# Part1_3210105209.net
KiCad netlist of a schematic drawn in Altium Designer
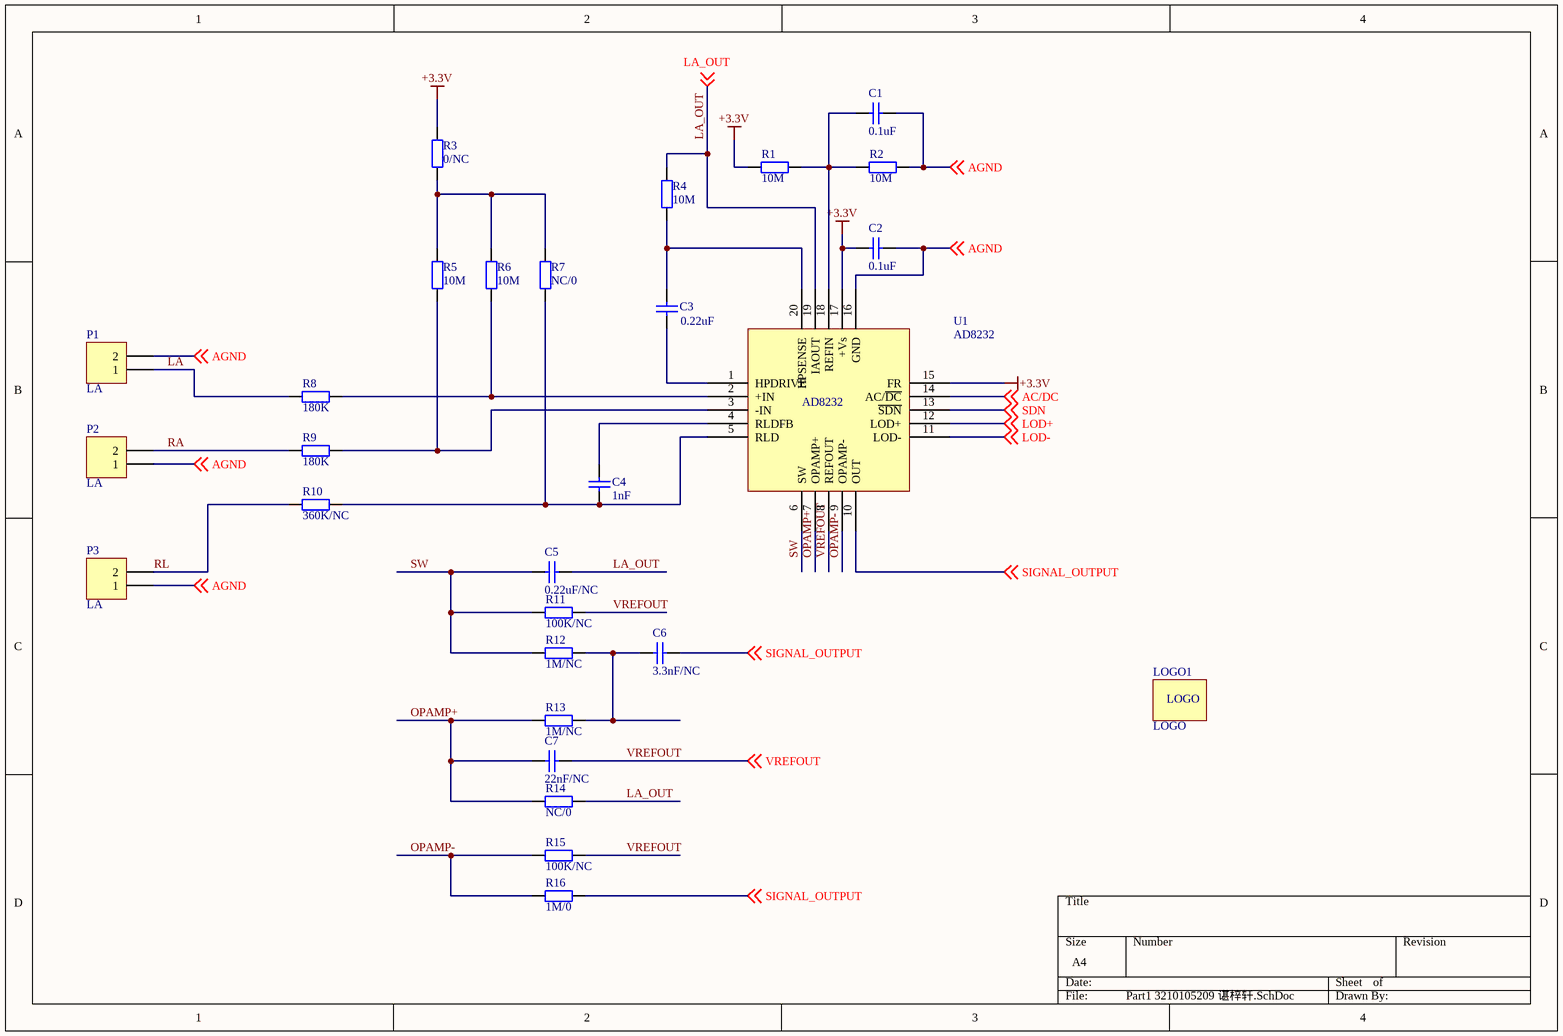
[diagram p0: Part1 3210105209 谌梓轩.SchDoc]

(export (version "E")
  (design (tool "Eeschema 10.0.6"))
  (components
    (comp (ref "C1")
      (value "0.1uF")
      (footprint "0603C")
      (description "Capacitor")
      (fields (field (name "PUBLISHER") "Altium Limited"))
      (libsource (lib "ECG2.0_1") (part "Cap"))
    )
    (comp (ref "C2")
      (value "0.1uF")
      (footprint "0603C")
      (description "Capacitor")
      (fields (field (name "PUBLISHER") "Altium Limited"))
      (libsource (lib "ECG2.0_1") (part "Cap"))
    )
    (comp (ref "C3")
      (value "0.22uF")
      (footprint "0603C")
      (description "Capacitor")
      (fields (field (name "PUBLISHER") "Altium Limited"))
      (libsource (lib "ECG2.0_1") (part "Cap"))
    )
    (comp (ref "C4")
      (value "1nF")
      (footprint "0603C")
      (description "Capacitor")
      (fields (field (name "PUBLISHER") "Altium Limited"))
      (libsource (lib "ECG2.0_1") (part "Cap"))
    )
    (comp (ref "C5")
      (value "0.22uF/NC")
      (footprint "0603C")
      (description "Capacitor")
      (fields (field (name "PUBLISHER") "Altium Limited"))
      (libsource (lib "ECG2.0_1") (part "Cap"))
    )
    (comp (ref "C6")
      (value "3.3nF/NC")
      (footprint "0603C")
      (description "Capacitor")
      (fields (field (name "PUBLISHER") "Altium Limited"))
      (libsource (lib "ECG2.0_1") (part "Cap"))
    )
    (comp (ref "C7")
      (value "22nF/NC")
      (footprint "0603C")
      (description "Capacitor")
      (fields (field (name "PUBLISHER") "Altium Limited"))
      (libsource (lib "ECG2.0_1") (part "Cap"))
    )
    (comp (ref "LOGO1") (value "LOGO") (footprint "LOGO") (libsource (lib "ECG2.0_1") (part "LOGO")))
    (comp (ref "P1")
      (value "LA")
      (footprint "SIP2")
      (description "Header, 2-Pin")
      (fields (field (name "PUBLISHER") "Altium Limited"))
      (libsource (lib "ECG2.0_1") (part "Header 2"))
    )
    (comp (ref "P2")
      (value "LA")
      (footprint "SIP2")
      (description "Header, 2-Pin")
      (fields (field (name "PUBLISHER") "Altium Limited"))
      (libsource (lib "ECG2.0_1") (part "Header 2"))
    )
    (comp (ref "P3")
      (value "LA")
      (footprint "SIP2")
      (description "Header, 2-Pin")
      (fields (field (name "PUBLISHER") "Altium Limited"))
      (libsource (lib "ECG2.0_1") (part "Header 2"))
    )
    (comp (ref "R1")
      (value "10M")
      (footprint "0603R")
      (description "Resistor")
      (fields (field (name "PUBLISHER") "Altium Limited"))
      (libsource (lib "") (part "Res2_1"))
    )
    (comp (ref "R2")
      (value "10M")
      (footprint "0603R")
      (description "Resistor")
      (fields (field (name "PUBLISHER") "Altium Limited"))
      (libsource (lib "") (part "Res2_1"))
    )
    (comp (ref "R3")
      (value "0/NC")
      (footprint "0603R")
      (description "Resistor")
      (fields (field (name "PUBLISHER") "Altium Limited"))
      (libsource (lib "ECG2.0_1") (part "Res2"))
    )
    (comp (ref "R4")
      (value "10M")
      (footprint "0603R")
      (description "Resistor")
      (fields (field (name "PUBLISHER") "Altium Limited"))
      (libsource (lib "ECG2.0_1") (part "Res2"))
    )
    (comp (ref "R5")
      (value "10M")
      (footprint "0603R")
      (description "Resistor")
      (fields (field (name "PUBLISHER") "Altium Limited"))
      (libsource (lib "ECG2.0_1") (part "Res2"))
    )
    (comp (ref "R6")
      (value "10M")
      (footprint "0603R")
      (description "Resistor")
      (fields (field (name "PUBLISHER") "Altium Limited"))
      (libsource (lib "ECG2.0_1") (part "Res2"))
    )
    (comp (ref "R7")
      (value "NC/0")
      (footprint "0603R")
      (description "Resistor")
      (fields (field (name "PUBLISHER") "Altium Limited"))
      (libsource (lib "ECG2.0_1") (part "Res2"))
    )
    (comp (ref "R8")
      (value "180K")
      (footprint "0603R")
      (description "Resistor")
      (fields (field (name "PUBLISHER") "Altium Limited"))
      (libsource (lib "") (part "Res2_1"))
    )
    (comp (ref "R9")
      (value "180K")
      (footprint "0603R")
      (description "Resistor")
      (fields (field (name "PUBLISHER") "Altium Limited"))
      (libsource (lib "") (part "Res2_1"))
    )
    (comp (ref "R10")
      (value "360K/NC")
      (footprint "0603R")
      (description "Resistor")
      (fields (field (name "PUBLISHER") "Altium Limited"))
      (libsource (lib "") (part "Res2_1"))
    )
    (comp (ref "R11")
      (value "100K/NC")
      (footprint "0603R")
      (description "Resistor")
      (fields (field (name "PUBLISHER") "Altium Limited"))
      (libsource (lib "") (part "Res2_1"))
    )
    (comp (ref "R12")
      (value "1M/NC")
      (footprint "0603R")
      (description "Resistor")
      (fields (field (name "PUBLISHER") "Altium Limited"))
      (libsource (lib "") (part "Res2_1"))
    )
    (comp (ref "R13")
      (value "1M/NC")
      (footprint "0603R")
      (description "Resistor")
      (fields (field (name "PUBLISHER") "Altium Limited"))
      (libsource (lib "") (part "Res2_1"))
    )
    (comp (ref "R14")
      (value "NC/0")
      (footprint "0603R")
      (description "Resistor")
      (fields (field (name "PUBLISHER") "Altium Limited"))
      (libsource (lib "") (part "Res2_1"))
    )
    (comp (ref "R15")
      (value "100K/NC")
      (footprint "0603R")
      (description "Resistor")
      (fields (field (name "PUBLISHER") "Altium Limited"))
      (libsource (lib "") (part "Res2_1"))
    )
    (comp (ref "R16")
      (value "1M/0")
      (footprint "0603R")
      (description "Resistor")
      (fields (field (name "PUBLISHER") "Altium Limited"))
      (libsource (lib "") (part "Res2_1"))
    )
    (comp (ref "U1") (value "AD8232") (footprint "QFN-20") (libsource (lib "ECG2.0") (part "AD8232")))
  )
  (nets
    (net (code "1") (name "+3.3V") (class "Default")
      (node (ref "C2") (pin "1") (pinfunction "1_1") (pintype "passive"))
      (node (ref "R1") (pin "1") (pinfunction "1_1") (pintype "passive"))
      (node (ref "R3") (pin "2") (pinfunction "2_2") (pintype "passive"))
      (node (ref "U1") (pin "15") (pinfunction "FR_15") (pintype "passive"))
      (node (ref "U1") (pin "17") (pinfunction "+Vs_17") (pintype "passive"))
    )
    (net (code "2") (name "/LA") (class "Default")
      (node (ref "P1") (pin "1") (pinfunction "1_1") (pintype "passive"))
      (node (ref "R8") (pin "1") (pinfunction "1_1") (pintype "passive"))
    )
    (net (code "3") (name "/OPAMP+") (class "Default")
      (node (ref "C7") (pin "1") (pinfunction "1_1") (pintype "passive"))
      (node (ref "R13") (pin "1") (pinfunction "1_1") (pintype "passive"))
      (node (ref "R14") (pin "1") (pinfunction "1_1") (pintype "passive"))
      (node (ref "U1") (pin "7") (pinfunction "OPAMP+_7") (pintype "passive"))
    )
    (net (code "4") (name "/OPAMP-") (class "Default")
      (node (ref "R15") (pin "1") (pinfunction "1_1") (pintype "passive"))
      (node (ref "R16") (pin "1") (pinfunction "1_1") (pintype "passive"))
      (node (ref "U1") (pin "9") (pinfunction "OPAMP-_9") (pintype "passive"))
    )
    (net (code "5") (name "/RA") (class "Default")
      (node (ref "P2") (pin "2") (pinfunction "2_2") (pintype "passive"))
      (node (ref "R9") (pin "1") (pinfunction "1_1") (pintype "passive"))
    )
    (net (code "6") (name "/RL") (class "Default")
      (node (ref "P3") (pin "2") (pinfunction "2_2") (pintype "passive"))
      (node (ref "R10") (pin "1") (pinfunction "1_1") (pintype "passive"))
    )
    (net (code "7") (name "/SW") (class "Default")
      (node (ref "C5") (pin "1") (pinfunction "1_1") (pintype "passive"))
      (node (ref "R11") (pin "1") (pinfunction "1_1") (pintype "passive"))
      (node (ref "R12") (pin "1") (pinfunction "1_1") (pintype "passive"))
      (node (ref "U1") (pin "6") (pinfunction "SW_6") (pintype "passive"))
    )
    (net (code "8") (name "AC{slash}DC") (class "Default")
      (node (ref "U1") (pin "14") (pinfunction "AC/~{DC}_14") (pintype "passive"))
    )
    (net (code "9") (name "AGND") (class "Default")
      (node (ref "C1") (pin "2") (pinfunction "2_2") (pintype "passive"))
      (node (ref "C2") (pin "2") (pinfunction "2_2") (pintype "passive"))
      (node (ref "P1") (pin "2") (pinfunction "2_2") (pintype "passive"))
      (node (ref "P2") (pin "1") (pinfunction "1_1") (pintype "passive"))
      (node (ref "P3") (pin "1") (pinfunction "1_1") (pintype "passive"))
      (node (ref "R2") (pin "2") (pinfunction "2_2") (pintype "passive"))
      (node (ref "U1") (pin "16") (pinfunction "GND_16") (pintype "passive"))
    )
    (net (code "10") (name "LA_OUT") (class "Default")
      (node (ref "C5") (pin "2") (pinfunction "2_2") (pintype "passive"))
      (node (ref "R14") (pin "2") (pinfunction "2_2") (pintype "passive"))
      (node (ref "R4") (pin "2") (pinfunction "2_2") (pintype "passive"))
      (node (ref "U1") (pin "19") (pinfunction "IAOUT_19") (pintype "passive"))
    )
    (net (code "11") (name "LOD+") (class "Default")
      (node (ref "U1") (pin "12") (pinfunction "LOD+_12") (pintype "passive"))
    )
    (net (code "12") (name "LOD-") (class "Default")
      (node (ref "U1") (pin "11") (pinfunction "LOD-_11") (pintype "passive"))
    )
    (net (code "13") (name "Net-(C6-Pad1)") (class "Default")
      (node (ref "C6") (pin "1") (pinfunction "1_1") (pintype "passive"))
      (node (ref "R12") (pin "2") (pinfunction "2_2") (pintype "passive"))
      (node (ref "R13") (pin "2") (pinfunction "2_2") (pintype "passive"))
    )
    (net (code "14") (name "Net-(R3-Pad1)") (class "Default")
      (node (ref "R3") (pin "1") (pinfunction "1_1") (pintype "passive"))
      (node (ref "R5") (pin "2") (pinfunction "2_2") (pintype "passive"))
      (node (ref "R6") (pin "2") (pinfunction "2_2") (pintype "passive"))
      (node (ref "R7") (pin "2") (pinfunction "2_2") (pintype "passive"))
    )
    (net (code "15") (name "Net-(U1-+IN)") (class "Default")
      (node (ref "R6") (pin "1") (pinfunction "1_1") (pintype "passive"))
      (node (ref "R8") (pin "2") (pinfunction "2_2") (pintype "passive"))
      (node (ref "U1") (pin "2") (pinfunction "+IN_2") (pintype "passive"))
    )
    (net (code "16") (name "Net-(U1--IN)") (class "Default")
      (node (ref "R5") (pin "1") (pinfunction "1_1") (pintype "passive"))
      (node (ref "R9") (pin "2") (pinfunction "2_2") (pintype "passive"))
      (node (ref "U1") (pin "3") (pinfunction "-IN_3") (pintype "passive"))
    )
    (net (code "17") (name "Net-(U1-HPDRIVE)") (class "Default")
      (node (ref "C3") (pin "1") (pinfunction "1_1") (pintype "passive"))
      (node (ref "U1") (pin "1") (pinfunction "HPDRIVE_1") (pintype "passive"))
    )
    (net (code "18") (name "Net-(U1-HPSENSE)") (class "Default")
      (node (ref "C3") (pin "2") (pinfunction "2_2") (pintype "passive"))
      (node (ref "R4") (pin "1") (pinfunction "1_1") (pintype "passive"))
      (node (ref "U1") (pin "20") (pinfunction "HPSENSE_20") (pintype "passive"))
    )
    (net (code "19") (name "Net-(U1-REFIN)") (class "Default")
      (node (ref "C1") (pin "1") (pinfunction "1_1") (pintype "passive"))
      (node (ref "R1") (pin "2") (pinfunction "2_2") (pintype "passive"))
      (node (ref "R2") (pin "1") (pinfunction "1_1") (pintype "passive"))
      (node (ref "U1") (pin "18") (pinfunction "REFIN_18") (pintype "passive"))
    )
    (net (code "20") (name "Net-(U1-RLD)") (class "Default")
      (node (ref "C4") (pin "1") (pinfunction "1_1") (pintype "passive"))
      (node (ref "R10") (pin "2") (pinfunction "2_2") (pintype "passive"))
      (node (ref "R7") (pin "1") (pinfunction "1_1") (pintype "passive"))
      (node (ref "U1") (pin "5") (pinfunction "RLD_5") (pintype "passive"))
    )
    (net (code "21") (name "Net-(U1-RLDFB)") (class "Default")
      (node (ref "C4") (pin "2") (pinfunction "2_2") (pintype "passive"))
      (node (ref "U1") (pin "4") (pinfunction "RLDFB_4") (pintype "passive"))
    )
    (net (code "22") (name "SDN") (class "Default")
      (node (ref "U1") (pin "13") (pinfunction "~{SDN}_13") (pintype "passive"))
    )
    (net (code "23") (name "SIGNAL_OUTPUT") (class "Default")
      (node (ref "C6") (pin "2") (pinfunction "2_2") (pintype "passive"))
      (node (ref "R16") (pin "2") (pinfunction "2_2") (pintype "passive"))
      (node (ref "U1") (pin "10") (pinfunction "OUT_10") (pintype "passive"))
    )
    (net (code "24") (name "VREFOUT") (class "Default")
      (node (ref "C7") (pin "2") (pinfunction "2_2") (pintype "passive"))
      (node (ref "R11") (pin "2") (pinfunction "2_2") (pintype "passive"))
      (node (ref "R15") (pin "2") (pinfunction "2_2") (pintype "passive"))
      (node (ref "U1") (pin "8") (pinfunction "REFOUT_8") (pintype "passive"))
    )
  )
)
